# AD.net
KiCad netlist of a schematic drawn in Altium Designer
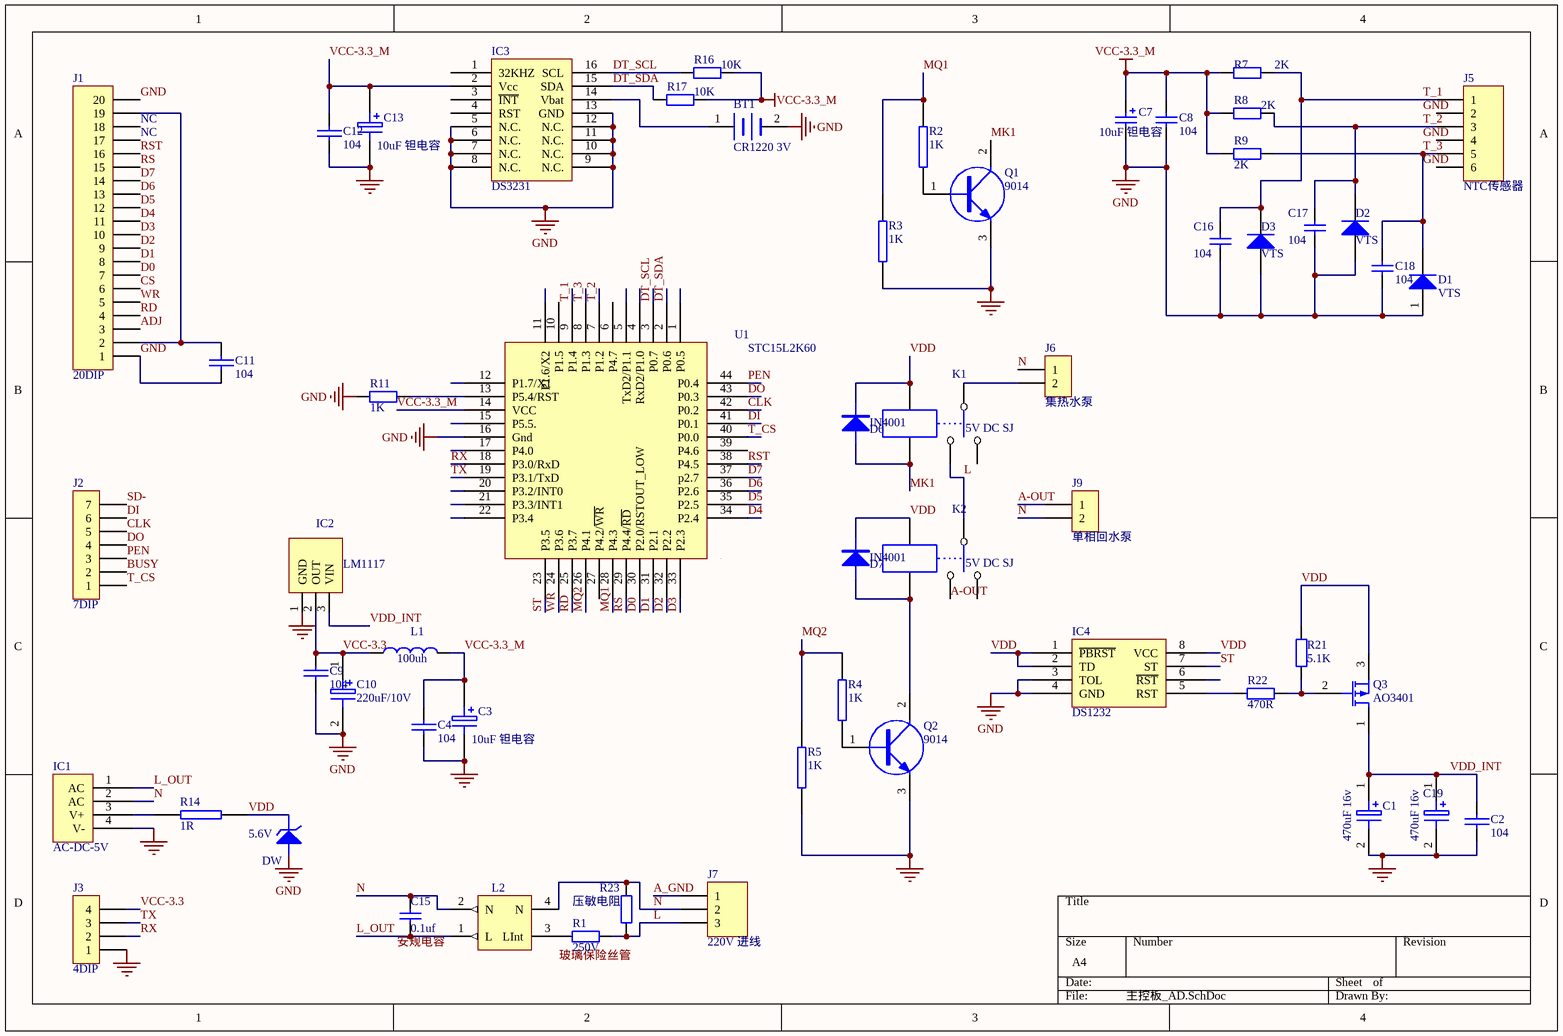
[diagram p0: 主控板_AD.SchDoc]

(export (version "E")
  (design (tool "Eeschema 10.0.6"))
  (components
    (comp (ref "BT1")
      (value "CR1220 3V")
      (footprint "bat")
      (description "Battery")
      (libsource (lib "*") (part "BATTERY"))
    )
    (comp (ref "C1") (value "470uF 16v") (footprint "RB.2/.4") (libsource (lib "") (part "EC_1")))
    (comp (ref "C2") (value "104") (footprint "0805") (libsource (lib "*") (part "CAP")))
    (comp (ref "C3") (value "10uF 钽电容") (footprint "1206") (libsource (lib "*") (part "EC")))
    (comp (ref "C4") (value "104") (footprint "0805") (libsource (lib "*") (part "CAP")))
    (comp (ref "C7")
      (value "10uF 钽电容")
      (footprint "1206")
      (description "Polarized Capacitor (Axial)")
      (fields (field (name "PUBLISHER") "Altium Limited"))
      (libsource (lib "Miscellaneous Devices") (part "Cap Pol2"))
    )
    (comp (ref "C8")
      (value "104")
      (footprint "0805")
      (description "Capacitor")
      (fields (field (name "PUBLISHER") "Altium Limited"))
      (libsource (lib "Miscellaneous Devices") (part "Cap"))
    )
    (comp (ref "C9") (value "104") (footprint "0805") (libsource (lib "*") (part "CAP")))
    (comp (ref "C10") (value "220uF/10V") (footprint "RB.2/.4") (libsource (lib "") (part "EC_1")))
    (comp (ref "C11") (value "104") (footprint "0805") (libsource (lib "*") (part "CAP")))
    (comp (ref "C12") (value "104") (footprint "0805") (libsource (lib "*") (part "CAP")))
    (comp (ref "C13") (value "10uF 钽电容") (footprint "1206") (libsource (lib "*") (part "EC")))
    (comp (ref "C15")
      (value "0.1uf")
      (footprint "DIP_10M")
      (description "Capacitor")
      (fields (field (name "PUBLISHER") "Altium Limited"))
      (libsource (lib "Miscellaneous Devices") (part "Cap"))
    )
    (comp (ref "C16")
      (value "104")
      (footprint "0805")
      (description "Capacitor")
      (fields (field (name "PUBLISHER") "Altium Limited"))
      (libsource (lib "Miscellaneous Devices") (part "Cap"))
    )
    (comp (ref "C17")
      (value "104")
      (footprint "0805")
      (description "Capacitor")
      (fields (field (name "PUBLISHER") "Altium Limited"))
      (libsource (lib "Miscellaneous Devices") (part "Cap"))
    )
    (comp (ref "C18")
      (value "104")
      (footprint "0805")
      (description "Capacitor")
      (fields (field (name "PUBLISHER") "Altium Limited"))
      (libsource (lib "Miscellaneous Devices") (part "Cap"))
    )
    (comp (ref "C19") (value "470uF 16v") (footprint "RB.2/.4") (libsource (lib "") (part "EC_1")))
    (comp (ref "D1")
      (value "VTS")
      (footprint "M7")
      (description "Default Diode")
      (fields (field (name "PUBLISHER") "Altium Limited"))
      (libsource (lib "") (part "Diode_1"))
    )
    (comp (ref "D2")
      (value "VTS")
      (footprint "M7")
      (description "Default Diode")
      (fields (field (name "PUBLISHER") "Altium Limited"))
      (libsource (lib "Miscellaneous Devices") (part "Diode"))
    )
    (comp (ref "D3")
      (value "VTS")
      (footprint "M7")
      (description "Default Diode")
      (fields (field (name "PUBLISHER") "Altium Limited"))
      (libsource (lib "Miscellaneous Devices") (part "Diode"))
    )
    (comp (ref "D6") (value "IN4001") (footprint "IN4001") (libsource (lib "KI-半导体管") (part "D")))
    (comp (ref "D7") (value "IN4001") (footprint "IN4001") (libsource (lib "KI-半导体管") (part "D")))
    (comp (ref "DW") (value "5.6V") (footprint "IN4001") (libsource (lib "KI-半导体管") (part "DW")))
    (comp (ref "IC1") (value "AC-DC-5V") (footprint "AC_DC_5V") (libsource (lib "电源芯片") (part "AC-DC-5V")))
    (comp (ref "IC2") (value "LM1117") (footprint "LM1117") (libsource (lib "*") (part "LM1117")))
    (comp (ref "IC3") (value "DS3231") (footprint "SOP16") (libsource (lib "MySch") (part "DS3231")))
    (comp (ref "IC4") (value "DS1232") (footprint "DS1302-150MIL") (libsource (lib "MySch") (part "DS1232")))
    (comp (ref "J1")
      (value "20DIP")
      (footprint "SIP20")
      (description "Connector")
      (libsource (lib "*") (part "CON20"))
    )
    (comp (ref "J2")
      (value "7DIP")
      (footprint "SIP7")
      (description "Connector")
      (libsource (lib "*") (part "CON7"))
    )
    (comp (ref "J3")
      (value "4DIP")
      (footprint "SIP4")
      (description "Connector")
      (libsource (lib "*") (part "CON4"))
    )
    (comp (ref "J5")
      (value "NTC传感器")
      (footprint "PCB_2.54_6")
      (description "Header, 6-Pin")
      (fields (field (name "PUBLISHER") "Altium Limited"))
      (libsource (lib "MySch") (part "Header 6"))
    )
    (comp (ref "J6")
      (value "集热水泵")
      (footprint "PCB_7.62*2")
      (description "Connector")
      (libsource (lib "*") (part "CON2"))
    )
    (comp (ref "J7")
      (value "220V 进线")
      (footprint "PCB_7.62*3")
      (description "Header, 3-Pin")
      (fields (field (name "PUBLISHER") "Altium Limited"))
      (libsource (lib "Miscellaneous Connectors") (part "Header 3"))
    )
    (comp (ref "J9")
      (value "单相回水泵")
      (footprint "PCB_7.62*2")
      (description "Connector")
      (libsource (lib "*") (part "CON2"))
    )
    (comp (ref "K1") (value "5V DC SJ") (footprint "继电器1-2") (libsource (lib "*") (part "RELAY-SPDT")))
    (comp (ref "K2") (value "5V DC SJ") (footprint "继电器1-2") (libsource (lib "*") (part "RELAY-SPDT")))
    (comp (ref "L1") (value "100uh") (footprint "0805") (libsource (lib "*") (part "B4")))
    (comp (ref "L2") (value "~") (footprint "UU9.8共模") (libsource (lib "MySch") (part "diangan")))
    (comp (ref "Q1")
      (value "9014")
      (footprint "9014A1")
      (description "NPN Transistor")
      (libsource (lib "*") (part "NPN"))
    )
    (comp (ref "Q2")
      (value "9014")
      (footprint "9014A1")
      (description "NPN Transistor")
      (libsource (lib "*") (part "NPN"))
    )
    (comp (ref "Q3")
      (value "AO3401")
      (footprint "9014A1")
      (description "P-Channel MOSFET")
      (fields (field (name "PUBLISHER") "Altium Limited"))
      (libsource (lib "Miscellaneous Devices") (part "MOSFET-P"))
    )
    (comp (ref "R1")
      (value "250V")
      (footprint "DIP_14mm")
      (description "Resistor")
      (fields (field (name "PUBLISHER") "Altium Limited"))
      (libsource (lib "Miscellaneous Devices") (part "Res2"))
    )
    (comp (ref "R2") (value "1K") (footprint "0805") (libsource (lib "*") (part "RES2")))
    (comp (ref "R3") (value "1K") (footprint "0805") (libsource (lib "*") (part "RES2")))
    (comp (ref "R4") (value "1K") (footprint "0805TLJW") (libsource (lib "*") (part "RES2")))
    (comp (ref "R5") (value "1K") (footprint "0805TLJW") (libsource (lib "*") (part "RES2")))
    (comp (ref "R7")
      (value "2K")
      (footprint "0805TLJW")
      (description "Resistor")
      (fields (field (name "PUBLISHER") "Altium Limited"))
      (libsource (lib "Miscellaneous Devices") (part "Res2"))
    )
    (comp (ref "R8")
      (value "2K")
      (footprint "0805")
      (description "Resistor")
      (fields (field (name "PUBLISHER") "Altium Limited"))
      (libsource (lib "Miscellaneous Devices") (part "Res2"))
    )
    (comp (ref "R9")
      (value "2K")
      (footprint "0805")
      (description "Resistor")
      (fields (field (name "PUBLISHER") "Altium Limited"))
      (libsource (lib "Miscellaneous Devices") (part "Res2"))
    )
    (comp (ref "R11")
      (value "1K")
      (footprint "0805")
      (description "Resistor")
      (fields (field (name "PUBLISHER") "Altium Limited"))
      (libsource (lib "Miscellaneous Devices") (part "Res2"))
    )
    (comp (ref "R14") (value "1R") (footprint "0805") (libsource (lib "*") (part "RES2")))
    (comp (ref "R16")
      (value "10K")
      (footprint "0805")
      (description "Resistor")
      (fields (field (name "PUBLISHER") "Altium Limited"))
      (libsource (lib "Miscellaneous Devices") (part "Res2"))
    )
    (comp (ref "R17")
      (value "10K")
      (footprint "0805")
      (description "Resistor")
      (fields (field (name "PUBLISHER") "Altium Limited"))
      (libsource (lib "Miscellaneous Devices") (part "Res2"))
    )
    (comp (ref "R21")
      (value "5.1K")
      (footprint "0805")
      (description "Resistor")
      (fields (field (name "PUBLISHER") "Altium Limited"))
      (libsource (lib "") (part "Res2_1"))
    )
    (comp (ref "R22")
      (value "470R")
      (footprint "0805")
      (description "Resistor")
      (fields (field (name "PUBLISHER") "Altium Limited"))
      (libsource (lib "Miscellaneous Devices") (part "Res2"))
    )
    (comp (ref "R23")
      (value "压敏电阻")
      (footprint "AXIAL-0.4")
      (description "Resistor")
      (fields (field (name "PUBLISHER") "Altium Limited"))
      (libsource (lib "") (part "Res2_1"))
    )
    (comp (ref "U1")
      (value "STC15L2K60")
      (footprint "LQFP44")
      (description "STC15L,44pin")
      (libsource (lib "MySch") (part "STC15L2K60"))
    )
  )
  (nets
    (net (code "1") (name "/A-OUT") (class "Default")
      (node (ref "J9") (pin "1") (pinfunction "1_1") (pintype "passive"))
      (node (ref "K2") (pin "3") (pinfunction "3_3") (pintype "passive"))
    )
    (net (code "2") (name "/ADJ") (class "Default")
      (node (ref "J1") (pin "3") (pinfunction "3_3") (pintype "passive"))
    )
    (net (code "3") (name "/A_GND") (class "Default")
      (node (ref "J7") (pin "1") (pinfunction "1_1") (pintype "passive"))
    )
    (net (code "4") (name "/BUSY") (class "Default")
      (node (ref "J2") (pin "2") (pinfunction "2_2") (pintype "passive"))
    )
    (net (code "5") (name "/CLK") (class "Default")
      (node (ref "J2") (pin "5") (pinfunction "5_5") (pintype "passive"))
      (node (ref "U1") (pin "42") (pinfunction "P0.2_42") (pintype "passive"))
    )
    (net (code "6") (name "/CS") (class "Default")
      (node (ref "J1") (pin "6") (pinfunction "6_6") (pintype "passive"))
    )
    (net (code "7") (name "/D0") (class "Default")
      (node (ref "J1") (pin "7") (pinfunction "7_7") (pintype "passive"))
      (node (ref "U1") (pin "30") (pinfunction "P2.0/RSTOUT_LOW_30") (pintype "passive"))
    )
    (net (code "8") (name "/D1") (class "Default")
      (node (ref "J1") (pin "8") (pinfunction "8_8") (pintype "passive"))
      (node (ref "U1") (pin "31") (pinfunction "P2.1_31") (pintype "passive"))
    )
    (net (code "9") (name "/D2") (class "Default")
      (node (ref "J1") (pin "9") (pinfunction "9_9") (pintype "passive"))
      (node (ref "U1") (pin "32") (pinfunction "P2.2_32") (pintype "passive"))
    )
    (net (code "10") (name "/D3") (class "Default")
      (node (ref "J1") (pin "10") (pinfunction "10_10") (pintype "passive"))
      (node (ref "U1") (pin "33") (pinfunction "P2.3_33") (pintype "passive"))
    )
    (net (code "11") (name "/D4") (class "Default")
      (node (ref "J1") (pin "11") (pinfunction "11_11") (pintype "passive"))
      (node (ref "U1") (pin "34") (pinfunction "P2.4_34") (pintype "passive"))
    )
    (net (code "12") (name "/D5") (class "Default")
      (node (ref "J1") (pin "12") (pinfunction "12_12") (pintype "passive"))
      (node (ref "U1") (pin "35") (pinfunction "P2.5_35") (pintype "passive"))
    )
    (net (code "13") (name "/D6") (class "Default")
      (node (ref "J1") (pin "13") (pinfunction "13_13") (pintype "passive"))
      (node (ref "U1") (pin "36") (pinfunction "P2.6_36") (pintype "passive"))
    )
    (net (code "14") (name "/D7") (class "Default")
      (node (ref "J1") (pin "14") (pinfunction "14_14") (pintype "passive"))
      (node (ref "U1") (pin "37") (pinfunction "p2.7_37") (pintype "passive"))
    )
    (net (code "15") (name "/DI") (class "Default")
      (node (ref "J2") (pin "6") (pinfunction "6_6") (pintype "passive"))
      (node (ref "U1") (pin "41") (pinfunction "P0.1_41") (pintype "passive"))
    )
    (net (code "16") (name "/DO") (class "Default")
      (node (ref "J2") (pin "4") (pinfunction "4_4") (pintype "passive"))
      (node (ref "U1") (pin "43") (pinfunction "P0.3_43") (pintype "passive"))
    )
    (net (code "17") (name "/DT_SCL") (class "Default")
      (node (ref "IC3") (pin "16") (pinfunction "SCL_16") (pintype "passive"))
      (node (ref "R16") (pin "1") (pinfunction "1_1") (pintype "passive"))
      (node (ref "U1") (pin "3") (pinfunction "P0.7_3") (pintype "passive"))
    )
    (net (code "18") (name "/DT_SDA") (class "Default")
      (node (ref "IC3") (pin "15") (pinfunction "SDA_15") (pintype "passive"))
      (node (ref "R17") (pin "1") (pinfunction "1_1") (pintype "passive"))
      (node (ref "U1") (pin "2") (pinfunction "P0.6_2") (pintype "passive"))
    )
    (net (code "19") (name "/L") (class "Default")
      (node (ref "J7") (pin "3") (pinfunction "3_3") (pintype "passive"))
      (node (ref "K1") (pin "3") (pinfunction "3_3") (pintype "passive"))
      (node (ref "K2") (pin "1") (pinfunction "1_1") (pintype "passive"))
      (node (ref "R1") (pin "2") (pinfunction "2_2") (pintype "passive"))
      (node (ref "R23") (pin "1") (pinfunction "1_1") (pintype "passive"))
    )
    (net (code "20") (name "/L_OUT") (class "Default")
      (node (ref "C15") (pin "1") (pinfunction "1_1") (pintype "passive"))
      (node (ref "IC1") (pin "1") (pinfunction "AC_1") (pintype "passive"))
      (node (ref "L2") (pin "1") (pinfunction "L_1") (pintype "output"))
    )
    (net (code "21") (name "/MK1") (class "Default")
      (node (ref "D6") (pin "1") (pinfunction "A_1") (pintype "passive"))
      (node (ref "K1") (pin "5") (pinfunction "5_5") (pintype "passive"))
      (node (ref "Q1") (pin "2") (pinfunction "C_2") (pintype "passive"))
    )
    (net (code "22") (name "/MQ1") (class "Default")
      (node (ref "R2") (pin "2") (pinfunction "2_2") (pintype "passive"))
      (node (ref "R3") (pin "1") (pinfunction "1_1") (pintype "passive"))
      (node (ref "U1") (pin "28") (pinfunction "P4.3_28") (pintype "passive"))
    )
    (net (code "23") (name "/MQ2") (class "Default")
      (node (ref "R4") (pin "2") (pinfunction "2_2") (pintype "passive"))
      (node (ref "R5") (pin "1") (pinfunction "1_1") (pintype "passive"))
      (node (ref "U1") (pin "26") (pinfunction "P4.1_26") (pintype "passive"))
    )
    (net (code "24") (name "/N") (class "Default")
      (node (ref "C15") (pin "2") (pinfunction "2_2") (pintype "passive"))
      (node (ref "IC1") (pin "2") (pinfunction "AC_2") (pintype "passive"))
      (node (ref "J6") (pin "1") (pinfunction "1_1") (pintype "passive"))
      (node (ref "J7") (pin "2") (pinfunction "2_2") (pintype "passive"))
      (node (ref "J9") (pin "2") (pinfunction "2_2") (pintype "passive"))
      (node (ref "L2") (pin "2") (pinfunction "N_2") (pintype "output"))
      (node (ref "L2") (pin "4") (pinfunction "N_4") (pintype "passive"))
      (node (ref "R23") (pin "2") (pinfunction "2_2") (pintype "passive"))
    )
    (net (code "25") (name "/PEN") (class "Default")
      (node (ref "J2") (pin "3") (pinfunction "3_3") (pintype "passive"))
      (node (ref "U1") (pin "44") (pinfunction "P0.4_44") (pintype "passive"))
    )
    (net (code "26") (name "/RD") (class "Default")
      (node (ref "J1") (pin "4") (pinfunction "4_4") (pintype "passive"))
      (node (ref "U1") (pin "25") (pinfunction "P3.7_25") (pintype "passive"))
    )
    (net (code "27") (name "/RS") (class "Default")
      (node (ref "J1") (pin "15") (pinfunction "15_15") (pintype "passive"))
      (node (ref "U1") (pin "29") (pinfunction "P4.4/~{RD}_29") (pintype "passive"))
    )
    (net (code "28") (name "/RST") (class "Default")
      (node (ref "J1") (pin "16") (pinfunction "16_16") (pintype "passive"))
      (node (ref "U1") (pin "38") (pinfunction "P4.5_38") (pintype "passive"))
    )
    (net (code "29") (name "/RX") (class "Default")
      (node (ref "J3") (pin "2") (pinfunction "2_2") (pintype "passive"))
      (node (ref "U1") (pin "18") (pinfunction "P3.0/RxD_18") (pintype "passive"))
    )
    (net (code "30") (name "/SD-") (class "Default")
      (node (ref "J2") (pin "7") (pinfunction "7_7") (pintype "passive"))
    )
    (net (code "31") (name "/ST") (class "Default")
      (node (ref "IC4") (pin "7") (pinfunction "ST_7") (pintype "passive"))
      (node (ref "U1") (pin "23") (pinfunction "P3.5_23") (pintype "passive"))
    )
    (net (code "32") (name "/TX") (class "Default")
      (node (ref "J3") (pin "3") (pinfunction "3_3") (pintype "passive"))
      (node (ref "U1") (pin "19") (pinfunction "P3.1/TxD_19") (pintype "passive"))
    )
    (net (code "33") (name "/T_1") (class "Default")
      (node (ref "C16") (pin "1") (pinfunction "1_1") (pintype "passive"))
      (node (ref "D3") (pin "2") (pinfunction "K_2") (pintype "passive"))
      (node (ref "J5") (pin "1") (pinfunction "1_1") (pintype "passive"))
      (node (ref "R7") (pin "2") (pinfunction "2_2") (pintype "passive"))
      (node (ref "U1") (pin "9") (pinfunction "P1.4_9") (pintype "passive"))
    )
    (net (code "34") (name "/T_2") (class "Default")
      (node (ref "C17") (pin "1") (pinfunction "1_1") (pintype "passive"))
      (node (ref "D2") (pin "2") (pinfunction "K_2") (pintype "passive"))
      (node (ref "J5") (pin "3") (pinfunction "3_3") (pintype "passive"))
      (node (ref "R8") (pin "2") (pinfunction "2_2") (pintype "passive"))
      (node (ref "U1") (pin "7") (pinfunction "P1.2_7") (pintype "passive"))
    )
    (net (code "35") (name "/T_CS") (class "Default")
      (node (ref "J2") (pin "1") (pinfunction "1_1") (pintype "passive"))
      (node (ref "U1") (pin "40") (pinfunction "P0.0_40") (pintype "passive"))
    )
    (net (code "36") (name "/VCC-3.3") (class "Default")
      (node (ref "C10") (pin "1") (pinfunction "1_1") (pintype "passive"))
      (node (ref "C9") (pin "1") (pinfunction "1_1") (pintype "passive"))
      (node (ref "IC2") (pin "2") (pinfunction "OUT_2") (pintype "passive"))
      (node (ref "J3") (pin "4") (pinfunction "4_4") (pintype "passive"))
      (node (ref "L1") (pin "1") (pinfunction "1_1") (pintype "passive"))
    )
    (net (code "37") (name "/VDD") (class "Default")
      (node (ref "D6") (pin "2") (pinfunction "K_2") (pintype "passive"))
      (node (ref "D7") (pin "2") (pinfunction "K_2") (pintype "passive"))
      (node (ref "DW") (pin "2") (pinfunction "K_2") (pintype "passive"))
      (node (ref "IC4") (pin "1") (pinfunction "~{PBRST}_1") (pintype "passive"))
      (node (ref "IC4") (pin "2") (pinfunction "TD_2") (pintype "passive"))
      (node (ref "IC4") (pin "8") (pinfunction "VCC_8") (pintype "passive"))
      (node (ref "K1") (pin "4") (pinfunction "4_4") (pintype "passive"))
      (node (ref "K2") (pin "4") (pinfunction "4_4") (pintype "passive"))
      (node (ref "Q3") (pin "3") (pinfunction "S_3") (pintype "passive"))
      (node (ref "R14") (pin "2") (pinfunction "2_2") (pintype "passive"))
      (node (ref "R21") (pin "2") (pinfunction "2_2") (pintype "passive"))
    )
    (net (code "38") (name "/VDD_INT") (class "Default")
      (node (ref "C1") (pin "1") (pinfunction "1_1") (pintype "passive"))
      (node (ref "C19") (pin "1") (pinfunction "1_1") (pintype "passive"))
      (node (ref "C2") (pin "1") (pinfunction "1_1") (pintype "passive"))
      (node (ref "IC2") (pin "3") (pinfunction "VIN_3") (pintype "passive"))
      (node (ref "Q3") (pin "1") (pinfunction "D_1") (pintype "passive"))
    )
    (net (code "39") (name "/WR") (class "Default")
      (node (ref "J1") (pin "5") (pinfunction "5_5") (pintype "passive"))
      (node (ref "U1") (pin "24") (pinfunction "P3.6_24") (pintype "passive"))
    )
    (net (code "40") (name "GND") (class "Default")
      (node (ref "BT1") (pin "2") (pinfunction "-_2") (pintype "passive"))
      (node (ref "C1") (pin "2") (pinfunction "2_2") (pintype "passive"))
      (node (ref "C10") (pin "2") (pinfunction "2_2") (pintype "passive"))
      (node (ref "C11") (pin "2") (pinfunction "2_2") (pintype "passive"))
      (node (ref "C12") (pin "2") (pinfunction "2_2") (pintype "passive"))
      (node (ref "C13") (pin "2") (pinfunction "2_2") (pintype "passive"))
      (node (ref "C16") (pin "2") (pinfunction "2_2") (pintype "passive"))
      (node (ref "C17") (pin "2") (pinfunction "2_2") (pintype "passive"))
      (node (ref "C18") (pin "1") (pinfunction "1_1") (pintype "passive"))
      (node (ref "C18") (pin "2") (pinfunction "2_2") (pintype "passive"))
      (node (ref "C19") (pin "2") (pinfunction "2_2") (pintype "passive"))
      (node (ref "C2") (pin "2") (pinfunction "2_2") (pintype "passive"))
      (node (ref "C3") (pin "2") (pinfunction "2_2") (pintype "passive"))
      (node (ref "C4") (pin "2") (pinfunction "2_2") (pintype "passive"))
      (node (ref "C7") (pin "2") (pinfunction "2_2") (pintype "passive"))
      (node (ref "C8") (pin "2") (pinfunction "2_2") (pintype "passive"))
      (node (ref "C9") (pin "2") (pinfunction "2_2") (pintype "passive"))
      (node (ref "D1") (pin "1") (pinfunction "A_1") (pintype "passive"))
      (node (ref "D1") (pin "2") (pinfunction "K_2") (pintype "passive"))
      (node (ref "D2") (pin "1") (pinfunction "A_1") (pintype "passive"))
      (node (ref "D3") (pin "1") (pinfunction "A_1") (pintype "passive"))
      (node (ref "DW") (pin "1") (pinfunction "A_1") (pintype "passive"))
      (node (ref "IC1") (pin "4") (pinfunction "V-_4") (pintype "passive"))
      (node (ref "IC2") (pin "1") (pinfunction "GND_1") (pintype "passive"))
      (node (ref "IC3") (pin "10") (pinfunction "N.C._10") (pintype "passive"))
      (node (ref "IC3") (pin "11") (pinfunction "N.C._11") (pintype "passive"))
      (node (ref "IC3") (pin "12") (pinfunction "N.C._12") (pintype "passive"))
      (node (ref "IC3") (pin "13") (pinfunction "GND_13") (pintype "passive"))
      (node (ref "IC3") (pin "5") (pinfunction "N.C._5") (pintype "passive"))
      (node (ref "IC3") (pin "6") (pinfunction "N.C._6") (pintype "passive"))
      (node (ref "IC3") (pin "7") (pinfunction "N.C._7") (pintype "passive"))
      (node (ref "IC3") (pin "8") (pinfunction "N.C._8") (pintype "passive"))
      (node (ref "IC3") (pin "9") (pinfunction "N.C._9") (pintype "passive"))
      (node (ref "IC4") (pin "3") (pinfunction "TOL_3") (pintype "passive"))
      (node (ref "IC4") (pin "4") (pinfunction "GND_4") (pintype "passive"))
      (node (ref "J1") (pin "1") (pinfunction "1_1") (pintype "passive"))
      (node (ref "J1") (pin "20") (pinfunction "20_20") (pintype "passive"))
      (node (ref "J3") (pin "1") (pinfunction "1_1") (pintype "passive"))
      (node (ref "J5") (pin "5") (pinfunction "5_5") (pintype "passive"))
      (node (ref "Q1") (pin "3") (pinfunction "E_3") (pintype "passive"))
      (node (ref "Q2") (pin "3") (pinfunction "E_3") (pintype "passive"))
      (node (ref "R11") (pin "1") (pinfunction "1_1") (pintype "passive"))
      (node (ref "R3") (pin "2") (pinfunction "2_2") (pintype "passive"))
      (node (ref "R5") (pin "2") (pinfunction "2_2") (pintype "passive"))
      (node (ref "R9") (pin "2") (pinfunction "2_2") (pintype "passive"))
      (node (ref "U1") (pin "16") (pinfunction "Gnd_16") (pintype "passive"))
      (node (ref "U1") (pin "8") (pinfunction "P1.3_8") (pintype "passive"))
    )
    (net (code "41") (name "Net-(BT1-+)") (class "Default")
      (node (ref "BT1") (pin "1") (pinfunction "+_1") (pintype "passive"))
      (node (ref "IC3") (pin "14") (pinfunction "Vbat_14") (pintype "passive"))
    )
    (net (code "42") (name "Net-(C11-Pad1)") (class "Default")
      (node (ref "C11") (pin "1") (pinfunction "1_1") (pintype "passive"))
      (node (ref "J1") (pin "19") (pinfunction "19_19") (pintype "passive"))
      (node (ref "J1") (pin "2") (pinfunction "2_2") (pintype "passive"))
    )
    (net (code "43") (name "Net-(D7-A)") (class "Default")
      (node (ref "D7") (pin "1") (pinfunction "A_1") (pintype "passive"))
      (node (ref "K2") (pin "5") (pinfunction "5_5") (pintype "passive"))
      (node (ref "Q2") (pin "2") (pinfunction "C_2") (pintype "passive"))
    )
    (net (code "44") (name "Net-(IC1-V+)") (class "Default")
      (node (ref "IC1") (pin "3") (pinfunction "V+_3") (pintype "passive"))
      (node (ref "R14") (pin "1") (pinfunction "1_1") (pintype "passive"))
    )
    (net (code "45") (name "Net-(IC4-RST)") (class "Default")
      (node (ref "IC4") (pin "5") (pinfunction "RST_5") (pintype "passive"))
      (node (ref "R22") (pin "1") (pinfunction "1_1") (pintype "passive"))
    )
    (net (code "46") (name "Net-(J6-Pad2)") (class "Default")
      (node (ref "J6") (pin "2") (pinfunction "2_2") (pintype "passive"))
      (node (ref "K1") (pin "1") (pinfunction "1_1") (pintype "passive"))
    )
    (net (code "47") (name "Net-(L2-LInt)") (class "Default")
      (node (ref "L2") (pin "3") (pinfunction "LInt_3") (pintype "passive"))
      (node (ref "R1") (pin "1") (pinfunction "1_1") (pintype "passive"))
    )
    (net (code "48") (name "Net-(Q1-B)") (class "Default")
      (node (ref "Q1") (pin "1") (pinfunction "B_1") (pintype "passive"))
      (node (ref "R2") (pin "1") (pinfunction "1_1") (pintype "passive"))
    )
    (net (code "49") (name "Net-(Q2-B)") (class "Default")
      (node (ref "Q2") (pin "1") (pinfunction "B_1") (pintype "passive"))
      (node (ref "R4") (pin "1") (pinfunction "1_1") (pintype "passive"))
    )
    (net (code "50") (name "Net-(Q3-G)") (class "Default")
      (node (ref "Q3") (pin "2") (pinfunction "G_2") (pintype "passive"))
      (node (ref "R21") (pin "1") (pinfunction "1_1") (pintype "passive"))
      (node (ref "R22") (pin "2") (pinfunction "2_2") (pintype "passive"))
    )
    (net (code "51") (name "Net-(U1-P5.4{slash}RST)") (class "Default")
      (node (ref "R11") (pin "2") (pinfunction "2_2") (pintype "passive"))
      (node (ref "U1") (pin "13") (pinfunction "P5.4/RST_13") (pintype "passive"))
    )
    (net (code "52") (name "VCC-3.3_M") (class "Default")
      (node (ref "C12") (pin "1") (pinfunction "1_1") (pintype "passive"))
      (node (ref "C13") (pin "1") (pinfunction "1_1") (pintype "passive"))
      (node (ref "C3") (pin "1") (pinfunction "1_1") (pintype "passive"))
      (node (ref "C4") (pin "1") (pinfunction "1_1") (pintype "passive"))
      (node (ref "C7") (pin "1") (pinfunction "1_1") (pintype "passive"))
      (node (ref "C8") (pin "1") (pinfunction "1_1") (pintype "passive"))
      (node (ref "IC3") (pin "2") (pinfunction "Vcc_2") (pintype "passive"))
      (node (ref "L1") (pin "2") (pinfunction "2_2") (pintype "passive"))
      (node (ref "R16") (pin "2") (pinfunction "2_2") (pintype "passive"))
      (node (ref "R17") (pin "2") (pinfunction "2_2") (pintype "passive"))
      (node (ref "R7") (pin "1") (pinfunction "1_1") (pintype "passive"))
      (node (ref "R8") (pin "1") (pinfunction "1_1") (pintype "passive"))
      (node (ref "R9") (pin "1") (pinfunction "1_1") (pintype "passive"))
      (node (ref "U1") (pin "14") (pinfunction "VCC_14") (pintype "passive"))
    )
    (net (code "53") (name "unconnected-(IC3-32KHZ-Pad1)") (class "Default")
      (node (ref "IC3") (pin "1") (pinfunction "32KHZ_1") (pintype "passive"))
    )
    (net (code "54") (name "unconnected-(IC3-RST-Pad4)") (class "Default")
      (node (ref "IC3") (pin "4") (pinfunction "RST_4") (pintype "passive"))
    )
    (net (code "55") (name "unconnected-(IC3-~{INT}-Pad3)") (class "Default")
      (node (ref "IC3") (pin "3") (pinfunction "~{INT}_3") (pintype "passive"))
    )
    (net (code "56") (name "unconnected-(IC4-~{RST}-Pad6)") (class "Default")
      (node (ref "IC4") (pin "6") (pinfunction "~{RST}_6") (pintype "passive"))
    )
    (net (code "57") (name "unconnected-(J1-Pad17)") (class "Default")
      (node (ref "J1") (pin "17") (pinfunction "17_17") (pintype "passive"))
    )
    (net (code "58") (name "unconnected-(J1-Pad18)") (class "Default")
      (node (ref "J1") (pin "18") (pinfunction "18_18") (pintype "passive"))
    )
    (net (code "59") (name "unconnected-(J5-Pad2)") (class "Default")
      (node (ref "J5") (pin "2") (pinfunction "2_2") (pintype "passive"))
    )
    (net (code "60") (name "unconnected-(J5-Pad4)") (class "Default")
      (node (ref "J5") (pin "4") (pinfunction "4_4") (pintype "passive"))
    )
    (net (code "61") (name "unconnected-(J5-Pad6)") (class "Default")
      (node (ref "J5") (pin "6") (pinfunction "6_6") (pintype "passive"))
    )
    (net (code "62") (name "unconnected-(K1-Pad2)") (class "Default")
      (node (ref "K1") (pin "2") (pinfunction "2_2") (pintype "passive"))
    )
    (net (code "63") (name "unconnected-(K2-Pad2)") (class "Default")
      (node (ref "K2") (pin "2") (pinfunction "2_2") (pintype "passive"))
    )
    (net (code "64") (name "unconnected-(U1-P0.5-Pad1)") (class "Default")
      (node (ref "U1") (pin "1") (pinfunction "P0.5_1") (pintype "passive"))
    )
    (net (code "65") (name "unconnected-(U1-P1.5-Pad10)") (class "Default")
      (node (ref "U1") (pin "10") (pinfunction "P1.5_10") (pintype "passive"))
    )
    (net (code "66") (name "unconnected-(U1-P1.6{slash}X2-Pad11)") (class "Default")
      (node (ref "U1") (pin "11") (pinfunction "P1.6/X2_11") (pintype "passive"))
    )
    (net (code "67") (name "unconnected-(U1-P1.7{slash}X1-Pad12)") (class "Default")
      (node (ref "U1") (pin "12") (pinfunction "P1.7/X1_12") (pintype "passive"))
    )
    (net (code "68") (name "unconnected-(U1-P3.2{slash}INT0-Pad20)") (class "Default")
      (node (ref "U1") (pin "20") (pinfunction "P3.2/INT0_20") (pintype "passive"))
    )
    (net (code "69") (name "unconnected-(U1-P3.3{slash}INT1-Pad21)") (class "Default")
      (node (ref "U1") (pin "21") (pinfunction "P3.3/INT1_21") (pintype "passive"))
    )
    (net (code "70") (name "unconnected-(U1-P3.4-Pad22)") (class "Default")
      (node (ref "U1") (pin "22") (pinfunction "P3.4_22") (pintype "passive"))
    )
    (net (code "71") (name "unconnected-(U1-P4.0-Pad17)") (class "Default")
      (node (ref "U1") (pin "17") (pinfunction "P4.0_17") (pintype "passive"))
    )
    (net (code "72") (name "unconnected-(U1-P4.2{slash}~{WR}-Pad27)") (class "Default")
      (node (ref "U1") (pin "27") (pinfunction "P4.2/~{WR}_27") (pintype "passive"))
    )
    (net (code "73") (name "unconnected-(U1-P4.6-Pad39)") (class "Default")
      (node (ref "U1") (pin "39") (pinfunction "P4.6_39") (pintype "passive"))
    )
    (net (code "74") (name "unconnected-(U1-P4.7-Pad6)") (class "Default")
      (node (ref "U1") (pin "6") (pinfunction "P4.7_6") (pintype "passive"))
    )
    (net (code "75") (name "unconnected-(U1-P5.5.-Pad15)") (class "Default")
      (node (ref "U1") (pin "15") (pinfunction "P5.5._15") (pintype "passive"))
    )
    (net (code "76") (name "unconnected-(U1-RxD2{slash}P1.0-Pad4)") (class "Default")
      (node (ref "U1") (pin "4") (pinfunction "RxD2/P1.0_4") (pintype "passive"))
    )
    (net (code "77") (name "unconnected-(U1-TxD2{slash}P1.1-Pad5)") (class "Default")
      (node (ref "U1") (pin "5") (pinfunction "TxD2/P1.1_5") (pintype "passive"))
    )
  )
)
